# MIDIpod.net
KiCad netlist of a schematic drawn in EAGLE
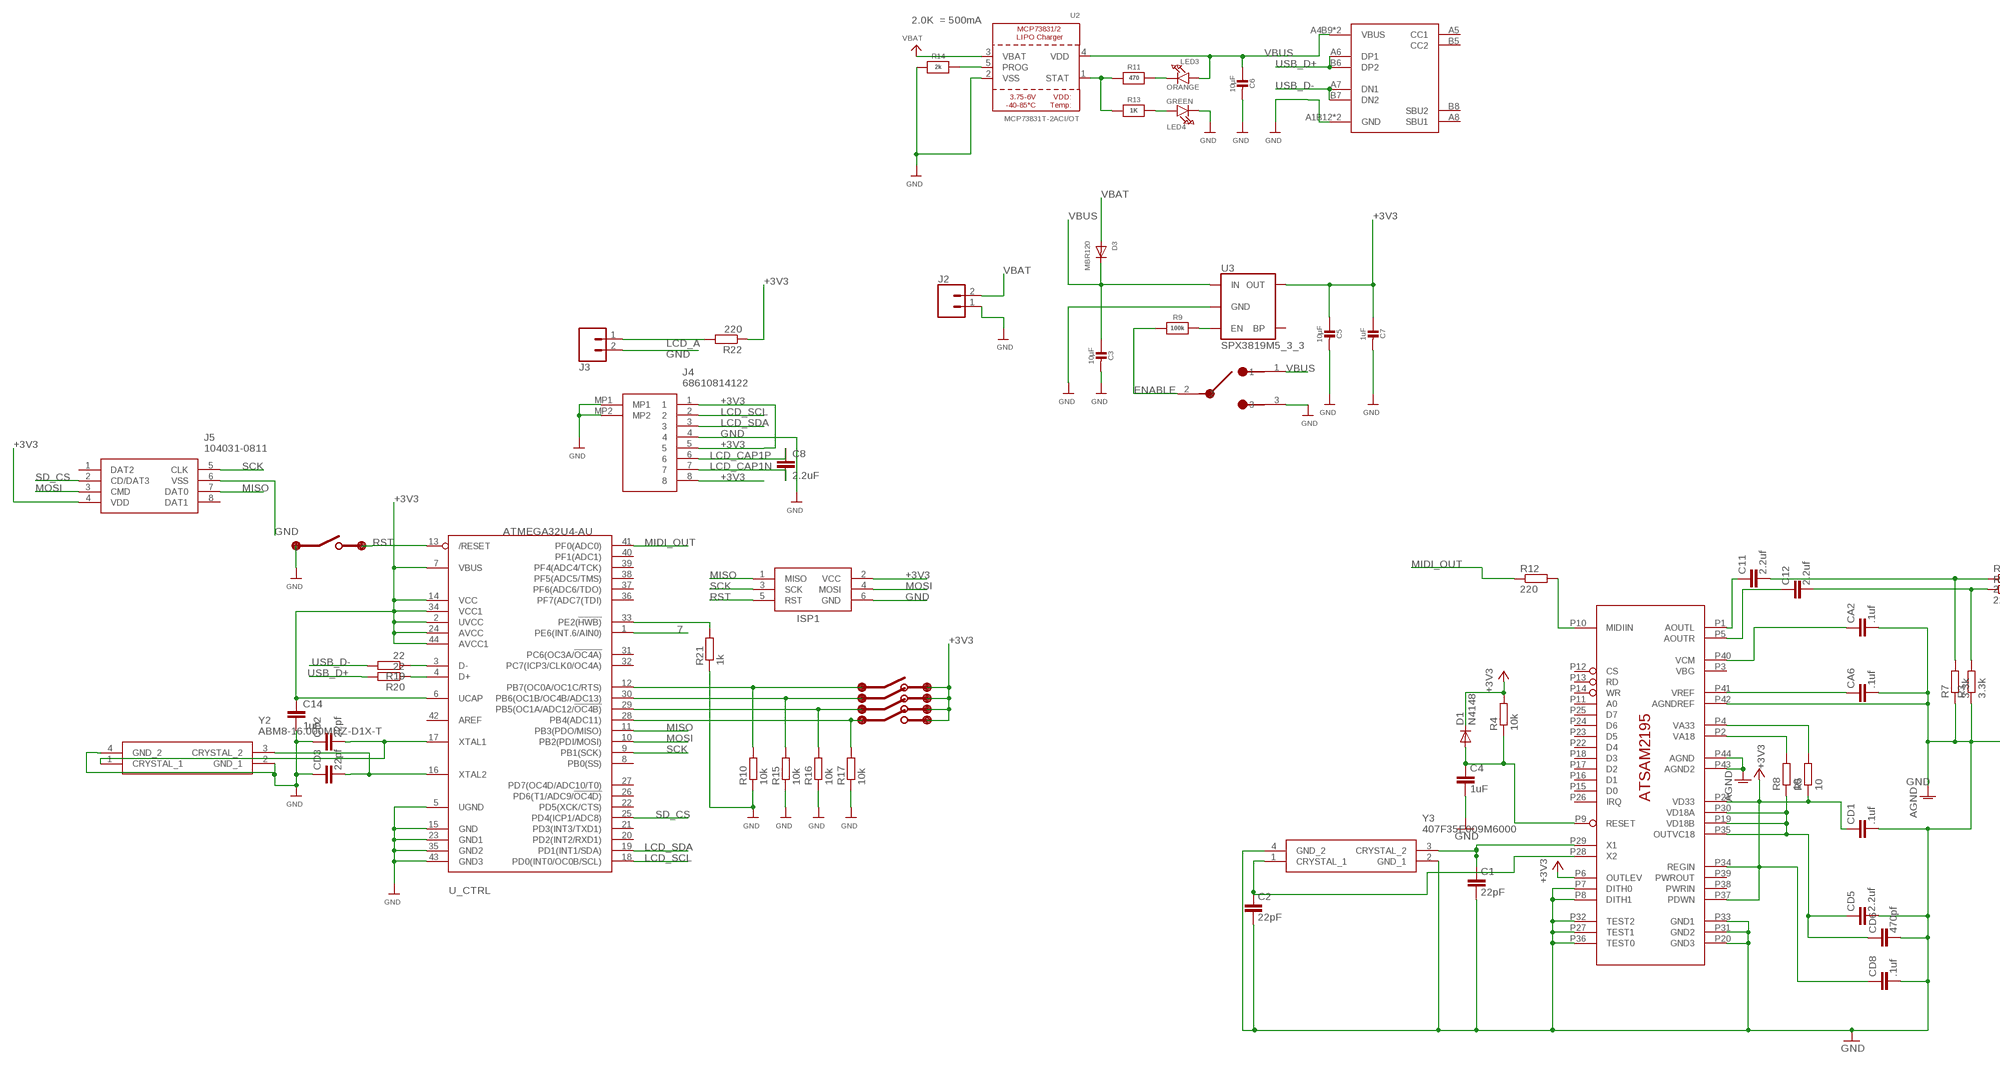
[diagram p0: schematic, sheet 1, part 1 of 2]
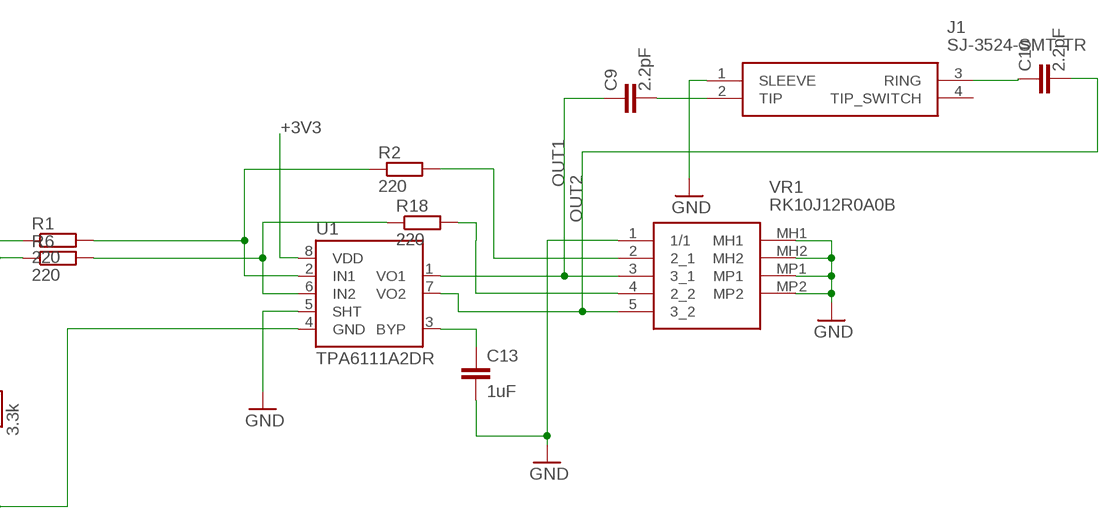
[diagram p1: schematic, sheet 1, part 2 of 2]

(export (version "E")
  (design (tool "Eeschema 10.0.6"))
  (components
    (comp (ref "BUTTON1")
      (value "1U_PAD")
      (footprint "eagle-import:SILICONE_SWITCH")
      (libsource (lib "eagle-import") (part "1U_PAD"))
    )
    (comp (ref "BUTTON2")
      (value "1U_PAD")
      (footprint "eagle-import:SILICONE_SWITCH")
      (libsource (lib "eagle-import") (part "1U_PAD"))
    )
    (comp (ref "BUTTON3")
      (value "1U_PAD")
      (footprint "eagle-import:SILICONE_SWITCH")
      (libsource (lib "eagle-import") (part "1U_PAD"))
    )
    (comp (ref "BUTTON4")
      (value "1U_PAD")
      (footprint "eagle-import:SILICONE_SWITCH")
      (libsource (lib "eagle-import") (part "1U_PAD"))
    )
    (comp (ref "BUTTON5")
      (value "1U_PAD")
      (footprint "eagle-import:SILICONE_SWITCH")
      (libsource (lib "eagle-import") (part "1U_PAD"))
    )
    (comp (ref "C1")
      (value "22pF")
      (footprint "eagle-import:C0603")
      (libsource (lib "eagle-import") (part "C-EUC0603"))
    )
    (comp (ref "C2")
      (value "22pF")
      (footprint "eagle-import:C0603")
      (libsource (lib "eagle-import") (part "C-EUC0603"))
    )
    (comp (ref "C3")
      (value "10µF")
      (footprint "eagle-import:0805-NO")
      (libsource (lib "eagle-import") (part "CAP_CERAMIC0805-NOOUTLINE"))
    )
    (comp (ref "C4")
      (value "1uF")
      (footprint "eagle-import:C0603")
      (libsource (lib "eagle-import") (part "C-EUC0603"))
    )
    (comp (ref "C5")
      (value "10µF")
      (footprint "eagle-import:0805-NO")
      (libsource (lib "eagle-import") (part "CAP_CERAMIC0805-NOOUTLINE"))
    )
    (comp (ref "C6")
      (value "10µF")
      (footprint "eagle-import:0805-NO")
      (libsource (lib "eagle-import") (part "CAP_CERAMIC0805-NOOUTLINE"))
    )
    (comp (ref "C7")
      (value "1uF")
      (footprint "eagle-import:0805-NO")
      (libsource (lib "eagle-import") (part "CAP_CERAMIC0805-NOOUTLINE"))
    )
    (comp (ref "C8")
      (value "2.2uF")
      (footprint "eagle-import:0805")
      (libsource (lib "eagle-import") (part "2.2UF-0805-25V-(+80/-20%)"))
    )
    (comp (ref "C9")
      (value "2.2pF")
      (footprint "eagle-import:C0603")
      (libsource (lib "eagle-import") (part "C-EUC0603"))
    )
    (comp (ref "C10")
      (value "2.2pF")
      (footprint "eagle-import:C0603")
      (libsource (lib "eagle-import") (part "C-EUC0603"))
    )
    (comp (ref "C11")
      (value "2.2uf")
      (footprint "eagle-import:C0603")
      (libsource (lib "eagle-import") (part "C-EUC0603"))
    )
    (comp (ref "C12")
      (value "2.2uf")
      (footprint "eagle-import:C0603")
      (libsource (lib "eagle-import") (part "C-EUC0603"))
    )
    (comp (ref "C13")
      (value "1uF")
      (footprint "eagle-import:0402")
      (libsource (lib "eagle-import") (part "0.1UF-0402-16V-10%"))
    )
    (comp (ref "C14")
      (value "1uF")
      (footprint "eagle-import:0402")
      (libsource (lib "eagle-import") (part "0.1UF-0402-16V-10%"))
    )
    (comp (ref "CA2")
      (value ".1uf")
      (footprint "eagle-import:C0603")
      (libsource (lib "eagle-import") (part "C-EUC0603"))
    )
    (comp (ref "CA6")
      (value ".1uf")
      (footprint "eagle-import:C0603")
      (libsource (lib "eagle-import") (part "C-EUC0603"))
    )
    (comp (ref "CD1")
      (value ".1uf")
      (footprint "eagle-import:C0603")
      (libsource (lib "eagle-import") (part "C-EUC0603"))
    )
    (comp (ref "CD2")
      (value "22pf")
      (footprint "eagle-import:C0603")
      (libsource (lib "eagle-import") (part "C-EUC0603"))
    )
    (comp (ref "CD3")
      (value "22pf")
      (footprint "eagle-import:C0603")
      (libsource (lib "eagle-import") (part "C-EUC0603"))
    )
    (comp (ref "CD5")
      (value "2.2uf")
      (footprint "eagle-import:C0603")
      (libsource (lib "eagle-import") (part "C-EUC0603"))
    )
    (comp (ref "CD6")
      (value "470pf")
      (footprint "eagle-import:C0603")
      (libsource (lib "eagle-import") (part "C-EUC0603"))
    )
    (comp (ref "CD8")
      (value ".1uf")
      (footprint "eagle-import:C0603")
      (libsource (lib "eagle-import") (part "C-EUC0603"))
    )
    (comp (ref "D1")
      (value "N4148")
      (footprint "eagle-import:SOD-123")
      (libsource (lib "eagle-import") (part "DIODESOD-123"))
    )
    (comp (ref "D3")
      (value "MBR120")
      (footprint "eagle-import:SOD-123")
      (libsource (lib "eagle-import") (part "DIODESOD-123"))
    )
    (comp (ref "ISP1")
      (value "AVRISP-6")
      (footprint "eagle-import:AVRISP")
      (libsource (lib "eagle-import") (part "AVRISP-6"))
    )
    (comp (ref "J1")
      (value "SJ-3524-SMT-TR")
      (footprint "eagle-import:SJ-3524-SMT-TR")
      (fields (field (name "MOUSER_PART_NUMBER") "490-SJ-3524-SMT-TR"))
      (libsource (lib "eagle-import") (part "SJ-3524-SMT-TR"))
    )
    (comp (ref "J2")
      (value "CONN_02")
      (footprint "eagle-import:1X02")
      (libsource (lib "eagle-import") (part "CONN_02"))
    )
    (comp (ref "J3")
      (value "CONN_02")
      (footprint "eagle-import:1X02")
      (libsource (lib "eagle-import") (part "CONN_02"))
    )
    (comp (ref "J4")
      (value "68610814122")
      (footprint "eagle-import:68610814122")
      (fields (field (name "MOUSER_PART_NUMBER") "710-68610814122"))
      (libsource (lib "eagle-import") (part "68610814122"))
    )
    (comp (ref "J5")
      (value "104031-0811")
      (footprint "eagle-import:1040310811")
      (fields (field (name "MOUSER_PART_NUMBER") "538-104031-0811"))
      (libsource (lib "eagle-import") (part "104031-0811"))
    )
    (comp (ref "LED3")
      (value "ORANGE")
      (footprint "eagle-import:CHIPLED_0805_NOOUTLINE")
      (libsource (lib "eagle-import") (part "LED0805_NOOUTLINE"))
    )
    (comp (ref "LED4")
      (value "GREEN")
      (footprint "eagle-import:CHIPLED_0805_NOOUTLINE")
      (libsource (lib "eagle-import") (part "LED0805_NOOUTLINE"))
    )
    (comp (ref "POWER_SW")
      (value "ALPSSLIDESW")
      (footprint "eagle-import:SWITCH-SSSS810701")
      (libsource (lib "eagle-import") (part "ALPSSLIDESW"))
    )
    (comp (ref "R1")
      (value "220")
      (footprint "eagle-import:R0603")
      (libsource (lib "eagle-import") (part "R-EU_R0603"))
    )
    (comp (ref "R2")
      (value "220")
      (footprint "eagle-import:R0603")
      (libsource (lib "eagle-import") (part "R-EU_R0603"))
    )
    (comp (ref "R3")
      (value "3.3k")
      (footprint "eagle-import:R0603")
      (libsource (lib "eagle-import") (part "R-EU_R0603"))
    )
    (comp (ref "R4")
      (value "10k")
      (footprint "eagle-import:R0603")
      (libsource (lib "eagle-import") (part "R-EU_R0603"))
    )
    (comp (ref "R5")
      (value "10")
      (footprint "eagle-import:R0603")
      (libsource (lib "eagle-import") (part "R-EU_R0603"))
    )
    (comp (ref "R6")
      (value "220")
      (footprint "eagle-import:R0603")
      (libsource (lib "eagle-import") (part "R-EU_R0603"))
    )
    (comp (ref "R7")
      (value "3.3k")
      (footprint "eagle-import:R0603")
      (libsource (lib "eagle-import") (part "R-EU_R0603"))
    )
    (comp (ref "R8")
      (value "10")
      (footprint "eagle-import:R0603")
      (libsource (lib "eagle-import") (part "R-EU_R0603"))
    )
    (comp (ref "R9")
      (value "100k")
      (footprint "eagle-import:0805-NO")
      (libsource (lib "eagle-import") (part "RESISTOR0805_NOOUTLINE"))
    )
    (comp (ref "R10")
      (value "10k")
      (footprint "eagle-import:R0603")
      (libsource (lib "eagle-import") (part "R-EU_R0603"))
    )
    (comp (ref "R11")
      (value "470")
      (footprint "eagle-import:0805-NO")
      (libsource (lib "eagle-import") (part "RESISTOR0805_NOOUTLINE"))
    )
    (comp (ref "R12")
      (value "220")
      (footprint "eagle-import:R0603")
      (libsource (lib "eagle-import") (part "R-EU_R0603"))
    )
    (comp (ref "R13")
      (value "1K")
      (footprint "eagle-import:0805-NO")
      (libsource (lib "eagle-import") (part "RESISTOR0805_NOOUTLINE"))
    )
    (comp (ref "R14")
      (value "2k")
      (footprint "eagle-import:0805-NO")
      (libsource (lib "eagle-import") (part "RESISTOR0805_NOOUTLINE"))
    )
    (comp (ref "R15")
      (value "10k")
      (footprint "eagle-import:R0603")
      (libsource (lib "eagle-import") (part "R-EU_R0603"))
    )
    (comp (ref "R16")
      (value "10k")
      (footprint "eagle-import:R0603")
      (libsource (lib "eagle-import") (part "R-EU_R0603"))
    )
    (comp (ref "R17")
      (value "10k")
      (footprint "eagle-import:R0603")
      (libsource (lib "eagle-import") (part "R-EU_R0603"))
    )
    (comp (ref "R18")
      (value "220")
      (footprint "eagle-import:R0603")
      (libsource (lib "eagle-import") (part "R-EU_R0603"))
    )
    (comp (ref "R19")
      (value "22")
      (footprint "eagle-import:R0603")
      (libsource (lib "eagle-import") (part "R-EU_R0603"))
    )
    (comp (ref "R20")
      (value "22")
      (footprint "eagle-import:R0603")
      (libsource (lib "eagle-import") (part "R-EU_R0603"))
    )
    (comp (ref "R21")
      (value "1k")
      (footprint "eagle-import:R0603")
      (libsource (lib "eagle-import") (part "R-EU_R0603"))
    )
    (comp (ref "R22")
      (value "220")
      (footprint "eagle-import:R0603")
      (libsource (lib "eagle-import") (part "R-EU_R0603"))
    )
    (comp (ref "U$1")
      (value "ATSAM2195")
      (footprint "eagle-import:ATSAM2195")
      (libsource (lib "eagle-import") (part "ATSAM2195"))
    )
    (comp (ref "U$43")
      (value "TYPE-C-31-M-12")
      (footprint "eagle-import:TYPE-C-31-M-12")
      (libsource (lib "eagle-import") (part "TYPE-C-31-M-12"))
    )
    (comp (ref "U1")
      (value "TPA6111A2DR")
      (footprint "eagle-import:SO08")
      (libsource (lib "eagle-import") (part "TPA6111SMD-T"))
    )
    (comp (ref "U2")
      (value "MCP73831T-2ACI/OT")
      (footprint "eagle-import:SOT23-5")
      (libsource (lib "eagle-import") (part "MCP73831/2"))
    )
    (comp (ref "U3")
      (value "SPX3819M5_3_3")
      (footprint "eagle-import:SOT23-5")
      (libsource (lib "eagle-import") (part "V_REG_SPX3819-SOT23-5"))
    )
    (comp (ref "U_CTRL")
      (value "ATMEGA32U4-AU")
      (footprint "eagle-import:TQFP44")
      (libsource (lib "eagle-import") (part "ATMEGA32U4-AU"))
    )
    (comp (ref "VR1")
      (value "RK10J12R0A0B")
      (footprint "eagle-import:RK10J12R0A0B")
      (fields (field (name "MOUSER_PART_NUMBER") "688-RK10J12R0A0B"))
      (libsource (lib "eagle-import") (part "RK10J12R0A0B"))
    )
    (comp (ref "Y2")
      (value "ABM8-16.000MHZ-D1X-T")
      (footprint "eagle-import:ABM816000MHZD1XT")
      (fields
        (field (name "MANUFACTURER_PART_NUMBER") "ABM8-16.000MHz-D1X-T")
        (field (name "MOUSER_PART_NUMBER") "815-ABM816000MHZD1XT")
      )
      (libsource (lib "eagle-import") (part "ABM8-16.000MHZ-D1X-T"))
    )
    (comp (ref "Y3")
      (value "407F35E009M6000")
      (footprint "eagle-import:407F35E009M6000")
      (fields (field (name "MOUSER_PART_NUMBER") "774-407F35E009M6000"))
      (libsource (lib "eagle-import") (part "407F35E009M6000"))
    )
  )
  (nets
    (net (code "1") (name "+3V3") (class "Default")
      (node (ref "BUTTON1") (pin "P$1") (pinfunction "P$1_P$1") (pintype "bidirectional"))
      (node (ref "BUTTON2") (pin "P$1") (pinfunction "P$1_P$1") (pintype "bidirectional"))
      (node (ref "BUTTON3") (pin "P$1") (pinfunction "P$1_P$1") (pintype "bidirectional"))
      (node (ref "BUTTON4") (pin "P$1") (pinfunction "P$1_P$1") (pintype "bidirectional"))
      (node (ref "C14") (pin "1") (pinfunction "1_1") (pintype "passive"))
      (node (ref "C5") (pin "1") (pinfunction "1_1") (pintype "passive"))
      (node (ref "C7") (pin "1") (pinfunction "1_1") (pintype "passive"))
      (node (ref "CD1") (pin "1") (pinfunction "1_1") (pintype "passive"))
      (node (ref "CD8") (pin "1") (pinfunction "1_1") (pintype "passive"))
      (node (ref "D1") (pin "C") (pinfunction "C_C") (pintype "passive"))
      (node (ref "ISP1") (pin "2") (pinfunction "VCC_2") (pintype "power_in"))
      (node (ref "J4") (pin "1") (pinfunction "1_1") (pintype "bidirectional"))
      (node (ref "J4") (pin "5") (pinfunction "5_5") (pintype "bidirectional"))
      (node (ref "J4") (pin "8") (pinfunction "8_8") (pintype "bidirectional"))
      (node (ref "J5") (pin "4") (pinfunction "VDD_4") (pintype "bidirectional"))
      (node (ref "R22") (pin "1") (pinfunction "1_1") (pintype "passive"))
      (node (ref "R4") (pin "2") (pinfunction "2_2") (pintype "passive"))
      (node (ref "R5") (pin "1") (pinfunction "1_1") (pintype "passive"))
      (node (ref "U$1") (pin "P21") (pinfunction "VD33_P21") (pintype "bidirectional"))
      (node (ref "U$1") (pin "P34") (pinfunction "REGIN_P34") (pintype "bidirectional"))
      (node (ref "U$1") (pin "P37") (pinfunction "PDWN_P37") (pintype "bidirectional"))
      (node (ref "U$1") (pin "P6") (pinfunction "OUTLEV_P6") (pintype "bidirectional"))
      (node (ref "U1") (pin "8") (pinfunction "VDD_8") (pintype "bidirectional"))
      (node (ref "U3") (pin "5") (pinfunction "OUT_5") (pintype "passive"))
      (node (ref "U_CTRL") (pin "14") (pinfunction "VCC_14") (pintype "bidirectional"))
      (node (ref "U_CTRL") (pin "2") (pinfunction "UVCC_2") (pintype "bidirectional"))
      (node (ref "U_CTRL") (pin "24") (pinfunction "AVCC_24") (pintype "bidirectional"))
      (node (ref "U_CTRL") (pin "34") (pinfunction "VCC1_34") (pintype "bidirectional"))
      (node (ref "U_CTRL") (pin "44") (pinfunction "AVCC1_44") (pintype "bidirectional"))
      (node (ref "U_CTRL") (pin "6") (pinfunction "UCAP_6") (pintype "bidirectional"))
      (node (ref "U_CTRL") (pin "7") (pinfunction "VBUS_7") (pintype "bidirectional"))
    )
    (net (code "2") (name "/7") (class "Default")
      (node (ref "U_CTRL") (pin "1") (pinfunction "PE6(INT.6/AIN0)_1") (pintype "bidirectional"))
    )
    (net (code "3") (name "/ENABLE") (class "Default")
      (node (ref "POWER_SW") (pin "2") (pinfunction "2_2") (pintype "bidirectional"))
      (node (ref "R9") (pin "2") (pinfunction "2_2") (pintype "passive"))
    )
    (net (code "4") (name "/LCD_A") (class "Default")
      (node (ref "J3") (pin "1") (pinfunction "1_1") (pintype "passive"))
      (node (ref "R22") (pin "2") (pinfunction "2_2") (pintype "passive"))
    )
    (net (code "5") (name "/LCD_CAP1N") (class "Default")
      (node (ref "C8") (pin "2") (pinfunction "2_2") (pintype "passive"))
      (node (ref "J4") (pin "7") (pinfunction "7_7") (pintype "bidirectional"))
    )
    (net (code "6") (name "/LCD_CAP1P") (class "Default")
      (node (ref "C8") (pin "1") (pinfunction "1_1") (pintype "passive"))
      (node (ref "J4") (pin "6") (pinfunction "6_6") (pintype "bidirectional"))
    )
    (net (code "7") (name "/LCD_SCL") (class "Default")
      (node (ref "J4") (pin "2") (pinfunction "2_2") (pintype "bidirectional"))
      (node (ref "U_CTRL") (pin "18") (pinfunction "PD0(INT0/OC0B/SCL)_18") (pintype "bidirectional"))
    )
    (net (code "8") (name "/LCD_SDA") (class "Default")
      (node (ref "J4") (pin "3") (pinfunction "3_3") (pintype "bidirectional"))
      (node (ref "U_CTRL") (pin "19") (pinfunction "PD1(INT1/SDA)_19") (pintype "bidirectional"))
    )
    (net (code "9") (name "/MIDI_OUT") (class "Default")
      (node (ref "R12") (pin "1") (pinfunction "1_1") (pintype "passive"))
      (node (ref "U_CTRL") (pin "41") (pinfunction "PF0(ADC0)_41") (pintype "bidirectional"))
    )
    (net (code "10") (name "/MISO") (class "Default")
      (node (ref "ISP1") (pin "1") (pinfunction "MISO_1") (pintype "input"))
      (node (ref "J5") (pin "7") (pinfunction "DAT0_7") (pintype "bidirectional"))
      (node (ref "U_CTRL") (pin "11") (pinfunction "PB3(PDO/MISO)_11") (pintype "bidirectional"))
    )
    (net (code "11") (name "/MOSI") (class "Default")
      (node (ref "ISP1") (pin "4") (pinfunction "MOSI_4") (pintype "output"))
      (node (ref "J5") (pin "3") (pinfunction "CMD_3") (pintype "bidirectional"))
      (node (ref "U_CTRL") (pin "10") (pinfunction "PB2(PDI/MOSI)_10") (pintype "bidirectional"))
    )
    (net (code "12") (name "/OUT1") (class "Default")
      (node (ref "C9") (pin "1") (pinfunction "1_1") (pintype "passive"))
      (node (ref "U1") (pin "1") (pinfunction "VO1_1") (pintype "bidirectional"))
      (node (ref "VR1") (pin "3") (pinfunction "3_1_3") (pintype "bidirectional"))
    )
    (net (code "13") (name "/OUT2") (class "Default")
      (node (ref "C10") (pin "2") (pinfunction "2_2") (pintype "passive"))
      (node (ref "U1") (pin "7") (pinfunction "VO2_7") (pintype "bidirectional"))
      (node (ref "VR1") (pin "5") (pinfunction "3_2_5") (pintype "bidirectional"))
    )
    (net (code "14") (name "/RST") (class "Default")
      (node (ref "BUTTON5") (pin "P$1") (pinfunction "P$1_P$1") (pintype "bidirectional"))
      (node (ref "ISP1") (pin "5") (pinfunction "RST_5") (pintype "output"))
      (node (ref "U_CTRL") (pin "13") (pinfunction "/RESET_13") (pintype "bidirectional"))
    )
    (net (code "15") (name "/SCK") (class "Default")
      (node (ref "ISP1") (pin "3") (pinfunction "SCK_3") (pintype "output"))
      (node (ref "J5") (pin "5") (pinfunction "CLK_5") (pintype "bidirectional"))
      (node (ref "U_CTRL") (pin "9") (pinfunction "PB1(SCK)_9") (pintype "bidirectional"))
    )
    (net (code "16") (name "/SD_CS") (class "Default")
      (node (ref "J5") (pin "2") (pinfunction "CD/DAT3_2") (pintype "bidirectional"))
      (node (ref "U_CTRL") (pin "25") (pinfunction "PD4(ICP1/ADC8)_25") (pintype "bidirectional"))
    )
    (net (code "17") (name "/USB_D+") (class "Default")
      (node (ref "R20") (pin "2") (pinfunction "2_2") (pintype "passive"))
      (node (ref "U$43") (pin "A6") (pinfunction "DP1_A6") (pintype "bidirectional"))
      (node (ref "U$43") (pin "B6") (pinfunction "DP2_B6") (pintype "bidirectional"))
    )
    (net (code "18") (name "/USB_D-") (class "Default")
      (node (ref "R19") (pin "2") (pinfunction "2_2") (pintype "passive"))
      (node (ref "U$43") (pin "A7") (pinfunction "DN1_A7") (pintype "bidirectional"))
      (node (ref "U$43") (pin "B7") (pinfunction "DN2_B7") (pintype "bidirectional"))
    )
    (net (code "19") (name "/VBUS") (class "Default")
      (node (ref "C3") (pin "1") (pinfunction "1_1") (pintype "passive"))
      (node (ref "C6") (pin "1") (pinfunction "1_1") (pintype "passive"))
      (node (ref "D3") (pin "C") (pinfunction "C_C") (pintype "passive"))
      (node (ref "LED3") (pin "A") (pinfunction "A_A") (pintype "passive"))
      (node (ref "POWER_SW") (pin "1") (pinfunction "1_1") (pintype "bidirectional"))
      (node (ref "U$43") (pin "A4B9") (pinfunction "VBUS_A4B9") (pintype "bidirectional"))
      (node (ref "U$43") (pin "B4A9") (pinfunction "VBUS_B4A9") (pintype "bidirectional"))
      (node (ref "U2") (pin "4") (pinfunction "VDD_4") (pintype "power_in"))
      (node (ref "U3") (pin "1") (pinfunction "IN_1") (pintype "input"))
    )
    (net (code "20") (name "AGND") (class "Default")
      (node (ref "BUTTON5") (pin "P$2") (pinfunction "P$2_P$2") (pintype "bidirectional"))
      (node (ref "C1") (pin "2") (pinfunction "2_2") (pintype "passive"))
      (node (ref "C13") (pin "2") (pinfunction "2_2") (pintype "passive"))
      (node (ref "C14") (pin "2") (pinfunction "2_2") (pintype "passive"))
      (node (ref "C2") (pin "2") (pinfunction "2_2") (pintype "passive"))
      (node (ref "C3") (pin "2") (pinfunction "2_2") (pintype "passive"))
      (node (ref "C4") (pin "2") (pinfunction "2_2") (pintype "passive"))
      (node (ref "C5") (pin "2") (pinfunction "2_2") (pintype "passive"))
      (node (ref "C6") (pin "2") (pinfunction "2_2") (pintype "passive"))
      (node (ref "C7") (pin "2") (pinfunction "2_2") (pintype "passive"))
      (node (ref "CA2") (pin "2") (pinfunction "2_2") (pintype "passive"))
      (node (ref "CA6") (pin "2") (pinfunction "2_2") (pintype "passive"))
      (node (ref "CD1") (pin "2") (pinfunction "2_2") (pintype "passive"))
      (node (ref "CD2") (pin "1") (pinfunction "1_1") (pintype "passive"))
      (node (ref "CD3") (pin "1") (pinfunction "1_1") (pintype "passive"))
      (node (ref "CD5") (pin "2") (pinfunction "2_2") (pintype "passive"))
      (node (ref "CD6") (pin "2") (pinfunction "2_2") (pintype "passive"))
      (node (ref "CD8") (pin "2") (pinfunction "2_2") (pintype "passive"))
      (node (ref "ISP1") (pin "6") (pinfunction "GND_6") (pintype "power_in"))
      (node (ref "J1") (pin "1") (pinfunction "SLEEVE_1") (pintype "bidirectional"))
      (node (ref "J2") (pin "1") (pinfunction "1_1") (pintype "passive"))
      (node (ref "J3") (pin "2") (pinfunction "2_2") (pintype "passive"))
      (node (ref "J4") (pin "4") (pinfunction "4_4") (pintype "bidirectional"))
      (node (ref "J4") (pin "MP1") (pinfunction "MP1_MP1") (pintype "bidirectional"))
      (node (ref "J4") (pin "MP2") (pinfunction "MP2_MP2") (pintype "bidirectional"))
      (node (ref "J5") (pin "6") (pinfunction "VSS_6") (pintype "bidirectional"))
      (node (ref "LED4") (pin "C") (pinfunction "C_C") (pintype "passive"))
      (node (ref "POWER_SW") (pin "3") (pinfunction "3_3") (pintype "bidirectional"))
      (node (ref "R10") (pin "1") (pinfunction "1_1") (pintype "passive"))
      (node (ref "R14") (pin "2") (pinfunction "2_2") (pintype "passive"))
      (node (ref "R15") (pin "1") (pinfunction "1_1") (pintype "passive"))
      (node (ref "R16") (pin "1") (pinfunction "1_1") (pintype "passive"))
      (node (ref "R17") (pin "1") (pinfunction "1_1") (pintype "passive"))
      (node (ref "R21") (pin "1") (pinfunction "1_1") (pintype "passive"))
      (node (ref "R3") (pin "1") (pinfunction "1_1") (pintype "passive"))
      (node (ref "R7") (pin "1") (pinfunction "1_1") (pintype "passive"))
      (node (ref "U$1") (pin "P20") (pinfunction "GND3_P20") (pintype "bidirectional"))
      (node (ref "U$1") (pin "P27") (pinfunction "TEST1_P27") (pintype "bidirectional"))
      (node (ref "U$1") (pin "P31") (pinfunction "GND2_P31") (pintype "bidirectional"))
      (node (ref "U$1") (pin "P32") (pinfunction "TEST2_P32") (pintype "bidirectional"))
      (node (ref "U$1") (pin "P33") (pinfunction "GND1_P33") (pintype "bidirectional"))
      (node (ref "U$1") (pin "P36") (pinfunction "TEST0_P36") (pintype "bidirectional"))
      (node (ref "U$1") (pin "P42") (pinfunction "AGNDREF_P42") (pintype "bidirectional"))
      (node (ref "U$1") (pin "P43") (pinfunction "AGND2_P43") (pintype "bidirectional"))
      (node (ref "U$1") (pin "P44") (pinfunction "AGND_P44") (pintype "bidirectional"))
      (node (ref "U$1") (pin "P7") (pinfunction "DITH0_P7") (pintype "bidirectional"))
      (node (ref "U$1") (pin "P8") (pinfunction "DITH1_P8") (pintype "bidirectional"))
      (node (ref "U$43") (pin "A1B12") (pinfunction "GND_A1B12") (pintype "bidirectional"))
      (node (ref "U$43") (pin "B1A12") (pinfunction "GND_B1A12") (pintype "bidirectional"))
      (node (ref "U1") (pin "4") (pinfunction "GND_4") (pintype "bidirectional"))
      (node (ref "U1") (pin "5") (pinfunction "SHT_5") (pintype "bidirectional"))
      (node (ref "U2") (pin "2") (pinfunction "VSS_2") (pintype "power_in"))
      (node (ref "U3") (pin "2") (pinfunction "GND_2") (pintype "input"))
      (node (ref "U_CTRL") (pin "15") (pinfunction "GND_15") (pintype "bidirectional"))
      (node (ref "U_CTRL") (pin "23") (pinfunction "GND1_23") (pintype "bidirectional"))
      (node (ref "U_CTRL") (pin "35") (pinfunction "GND2_35") (pintype "bidirectional"))
      (node (ref "U_CTRL") (pin "43") (pinfunction "GND3_43") (pintype "bidirectional"))
      (node (ref "U_CTRL") (pin "5") (pinfunction "UGND_5") (pintype "bidirectional"))
      (node (ref "VR1") (pin "1") (pinfunction "1/1_1") (pintype "bidirectional"))
      (node (ref "VR1") (pin "MH1") (pinfunction "MH1_MH1") (pintype "bidirectional"))
      (node (ref "VR1") (pin "MH2") (pinfunction "MH2_MH2") (pintype "bidirectional"))
      (node (ref "VR1") (pin "MP1") (pinfunction "MP1_MP1") (pintype "bidirectional"))
      (node (ref "VR1") (pin "MP2") (pinfunction "MP2_MP2") (pintype "bidirectional"))
      (node (ref "Y2") (pin "2") (pinfunction "GND_1_2") (pintype "bidirectional"))
      (node (ref "Y2") (pin "4") (pinfunction "GND_2_4") (pintype "bidirectional"))
      (node (ref "Y3") (pin "2") (pinfunction "GND_1_2") (pintype "bidirectional"))
      (node (ref "Y3") (pin "4") (pinfunction "GND_2_4") (pintype "bidirectional"))
    )
    (net (code "21") (name "Net-(C11-Pad2)") (class "Default")
      (node (ref "C11") (pin "2") (pinfunction "2_2") (pintype "passive"))
      (node (ref "R1") (pin "1") (pinfunction "1_1") (pintype "passive"))
      (node (ref "R7") (pin "2") (pinfunction "2_2") (pintype "passive"))
    )
    (net (code "22") (name "Net-(C12-Pad2)") (class "Default")
      (node (ref "C12") (pin "2") (pinfunction "2_2") (pintype "passive"))
      (node (ref "R3") (pin "2") (pinfunction "2_2") (pintype "passive"))
      (node (ref "R6") (pin "1") (pinfunction "1_1") (pintype "passive"))
    )
    (net (code "23") (name "Net-(J1-RING)") (class "Default")
      (node (ref "C10") (pin "1") (pinfunction "1_1") (pintype "passive"))
      (node (ref "J1") (pin "3") (pinfunction "RING_3") (pintype "bidirectional"))
    )
    (net (code "24") (name "Net-(J1-TIP)") (class "Default")
      (node (ref "C9") (pin "2") (pinfunction "2_2") (pintype "passive"))
      (node (ref "J1") (pin "2") (pinfunction "TIP_2") (pintype "bidirectional"))
    )
    (net (code "25") (name "Net-(LED3-PadC)") (class "Default")
      (node (ref "LED3") (pin "C") (pinfunction "C_C") (pintype "passive"))
      (node (ref "R11") (pin "1") (pinfunction "1_1") (pintype "passive"))
    )
    (net (code "26") (name "Net-(LED4-PadA)") (class "Default")
      (node (ref "LED4") (pin "A") (pinfunction "A_A") (pintype "passive"))
      (node (ref "R13") (pin "1") (pinfunction "1_1") (pintype "passive"))
    )
    (net (code "27") (name "Net-(U$1-AOUTL)") (class "Default")
      (node (ref "C11") (pin "1") (pinfunction "1_1") (pintype "passive"))
      (node (ref "U$1") (pin "P1") (pinfunction "AOUTL_P1") (pintype "bidirectional"))
    )
    (net (code "28") (name "Net-(U$1-AOUTR)") (class "Default")
      (node (ref "C12") (pin "1") (pinfunction "1_1") (pintype "passive"))
      (node (ref "U$1") (pin "P5") (pinfunction "AOUTR_P5") (pintype "bidirectional"))
    )
    (net (code "29") (name "Net-(U$1-MIDIIN)") (class "Default")
      (node (ref "R12") (pin "2") (pinfunction "2_2") (pintype "passive"))
      (node (ref "U$1") (pin "P10") (pinfunction "MIDIIN_P10") (pintype "bidirectional"))
    )
    (net (code "30") (name "Net-(U$1-OUTVC18)") (class "Default")
      (node (ref "CD5") (pin "1") (pinfunction "1_1") (pintype "passive"))
      (node (ref "CD6") (pin "1") (pinfunction "1_1") (pintype "passive"))
      (node (ref "R8") (pin "1") (pinfunction "1_1") (pintype "passive"))
      (node (ref "U$1") (pin "P19") (pinfunction "VD18B_P19") (pintype "bidirectional"))
      (node (ref "U$1") (pin "P30") (pinfunction "VD18A_P30") (pintype "bidirectional"))
      (node (ref "U$1") (pin "P35") (pinfunction "OUTVC18_P35") (pintype "bidirectional"))
    )
    (net (code "31") (name "Net-(U$1-RESET)") (class "Default")
      (node (ref "C4") (pin "1") (pinfunction "1_1") (pintype "passive"))
      (node (ref "D1") (pin "A") (pinfunction "A_A") (pintype "passive"))
      (node (ref "R4") (pin "1") (pinfunction "1_1") (pintype "passive"))
      (node (ref "U$1") (pin "P9") (pinfunction "RESET_P9") (pintype "bidirectional"))
    )
    (net (code "32") (name "Net-(U$1-VA18)") (class "Default")
      (node (ref "R8") (pin "2") (pinfunction "2_2") (pintype "passive"))
      (node (ref "U$1") (pin "P2") (pinfunction "VA18_P2") (pintype "bidirectional"))
    )
    (net (code "33") (name "Net-(U$1-VA33)") (class "Default")
      (node (ref "R5") (pin "2") (pinfunction "2_2") (pintype "passive"))
      (node (ref "U$1") (pin "P4") (pinfunction "VA33_P4") (pintype "bidirectional"))
    )
    (net (code "34") (name "Net-(U$1-VCM)") (class "Default")
      (node (ref "CA2") (pin "1") (pinfunction "1_1") (pintype "passive"))
      (node (ref "U$1") (pin "P40") (pinfunction "VCM_P40") (pintype "bidirectional"))
    )
    (net (code "35") (name "Net-(U$1-VREF)") (class "Default")
      (node (ref "CA6") (pin "1") (pinfunction "1_1") (pintype "passive"))
      (node (ref "U$1") (pin "P41") (pinfunction "VREF_P41") (pintype "bidirectional"))
    )
    (net (code "36") (name "Net-(U$1-X1)") (class "Default")
      (node (ref "C1") (pin "1") (pinfunction "1_1") (pintype "passive"))
      (node (ref "U$1") (pin "P29") (pinfunction "X1_P29") (pintype "bidirectional"))
      (node (ref "Y3") (pin "3") (pinfunction "CRYSTAL_2_3") (pintype "bidirectional"))
    )
    (net (code "37") (name "Net-(U$1-X2)") (class "Default")
      (node (ref "C2") (pin "1") (pinfunction "1_1") (pintype "passive"))
      (node (ref "U$1") (pin "P28") (pinfunction "X2_P28") (pintype "bidirectional"))
      (node (ref "Y3") (pin "1") (pinfunction "CRYSTAL_1_1") (pintype "bidirectional"))
    )
    (net (code "38") (name "Net-(U1-BYP)") (class "Default")
      (node (ref "C13") (pin "1") (pinfunction "1_1") (pintype "passive"))
      (node (ref "U1") (pin "3") (pinfunction "BYP_3") (pintype "bidirectional"))
    )
    (net (code "39") (name "Net-(U1-IN1)") (class "Default")
      (node (ref "R1") (pin "2") (pinfunction "2_2") (pintype "passive"))
      (node (ref "R2") (pin "1") (pinfunction "1_1") (pintype "passive"))
      (node (ref "U1") (pin "2") (pinfunction "IN1_2") (pintype "bidirectional"))
    )
    (net (code "40") (name "Net-(U1-IN2)") (class "Default")
      (node (ref "R18") (pin "1") (pinfunction "1_1") (pintype "passive"))
      (node (ref "R6") (pin "2") (pinfunction "2_2") (pintype "passive"))
      (node (ref "U1") (pin "6") (pinfunction "IN2_6") (pintype "bidirectional"))
    )
    (net (code "41") (name "Net-(U2-PROG)") (class "Default")
      (node (ref "R14") (pin "1") (pinfunction "1_1") (pintype "passive"))
      (node (ref "U2") (pin "5") (pinfunction "PROG_5") (pintype "input"))
    )
    (net (code "42") (name "Net-(U2-STAT)") (class "Default")
      (node (ref "R11") (pin "2") (pinfunction "2_2") (pintype "passive"))
      (node (ref "R13") (pin "2") (pinfunction "2_2") (pintype "passive"))
      (node (ref "U2") (pin "1") (pinfunction "STAT_1") (pintype "output"))
    )
    (net (code "43") (name "Net-(U3-EN)") (class "Default")
      (node (ref "R9") (pin "1") (pinfunction "1_1") (pintype "passive"))
      (node (ref "U3") (pin "3") (pinfunction "EN_3") (pintype "input"))
    )
    (net (code "44") (name "Net-(U_CTRL-D+)") (class "Default")
      (node (ref "R20") (pin "1") (pinfunction "1_1") (pintype "passive"))
      (node (ref "U_CTRL") (pin "4") (pinfunction "D+_4") (pintype "bidirectional"))
    )
    (net (code "45") (name "Net-(U_CTRL-D-)") (class "Default")
      (node (ref "R19") (pin "1") (pinfunction "1_1") (pintype "passive"))
      (node (ref "U_CTRL") (pin "3") (pinfunction "D-_3") (pintype "bidirectional"))
    )
    (net (code "46") (name "Net-(U_CTRL-PB4(ADC11))") (class "Default")
      (node (ref "BUTTON4") (pin "P$2") (pinfunction "P$2_P$2") (pintype "bidirectional"))
      (node (ref "R17") (pin "2") (pinfunction "2_2") (pintype "passive"))
      (node (ref "U_CTRL") (pin "28") (pinfunction "PB4(ADC11)_28") (pintype "bidirectional"))
    )
    (net (code "47") (name "Net-(U_CTRL-PB5(OC1A{slash}ADC12{slash}~{OC4B}))") (class "Default")
      (node (ref "BUTTON3") (pin "P$2") (pinfunction "P$2_P$2") (pintype "bidirectional"))
      (node (ref "R16") (pin "2") (pinfunction "2_2") (pintype "passive"))
      (node (ref "U_CTRL") (pin "29") (pinfunction "PB5(OC1A/ADC12/~{OC4B})_29") (pintype "bidirectional"))
    )
    (net (code "48") (name "Net-(U_CTRL-PB6(OC1B{slash}OC4B{slash}ADC13))") (class "Default")
      (node (ref "BUTTON2") (pin "P$2") (pinfunction "P$2_P$2") (pintype "bidirectional"))
      (node (ref "R15") (pin "2") (pinfunction "2_2") (pintype "passive"))
      (node (ref "U_CTRL") (pin "30") (pinfunction "PB6(OC1B/OC4B/ADC13)_30") (pintype "bidirectional"))
    )
    (net (code "49") (name "Net-(U_CTRL-PB7(OC0A{slash}OC1C{slash}RTS))") (class "Default")
      (node (ref "BUTTON1") (pin "P$2") (pinfunction "P$2_P$2") (pintype "bidirectional"))
      (node (ref "R10") (pin "2") (pinfunction "2_2") (pintype "passive"))
      (node (ref "U_CTRL") (pin "12") (pinfunction "PB7(OC0A/OC1C/RTS)_12") (pintype "bidirectional"))
    )
    (net (code "50") (name "Net-(U_CTRL-PE2(~{HWB}))") (class "Default")
      (node (ref "R21") (pin "2") (pinfunction "2_2") (pintype "passive"))
      (node (ref "U_CTRL") (pin "33") (pinfunction "PE2(~{HWB})_33") (pintype "bidirectional"))
    )
    (net (code "51") (name "Net-(U_CTRL-XTAL1)") (class "Default")
      (node (ref "CD2") (pin "2") (pinfunction "2_2") (pintype "passive"))
      (node (ref "U_CTRL") (pin "17") (pinfunction "XTAL1_17") (pintype "bidirectional"))
      (node (ref "Y2") (pin "1") (pinfunction "CRYSTAL_1_1") (pintype "bidirectional"))
    )
    (net (code "52") (name "Net-(U_CTRL-XTAL2)") (class "Default")
      (node (ref "CD3") (pin "2") (pinfunction "2_2") (pintype "passive"))
      (node (ref "U_CTRL") (pin "16") (pinfunction "XTAL2_16") (pintype "bidirectional"))
      (node (ref "Y2") (pin "3") (pinfunction "CRYSTAL_2_3") (pintype "bidirectional"))
    )
    (net (code "53") (name "Net-(VR1-2_1)") (class "Default")
      (node (ref "R2") (pin "2") (pinfunction "2_2") (pintype "passive"))
      (node (ref "VR1") (pin "2") (pinfunction "2_1_2") (pintype "bidirectional"))
    )
    (net (code "54") (name "Net-(VR1-2_2)") (class "Default")
      (node (ref "R18") (pin "2") (pinfunction "2_2") (pintype "passive"))
      (node (ref "VR1") (pin "4") (pinfunction "2_2_4") (pintype "bidirectional"))
    )
    (net (code "55") (name "VBAT") (class "Default")
      (node (ref "D3") (pin "A") (pinfunction "A_A") (pintype "passive"))
      (node (ref "J2") (pin "2") (pinfunction "2_2") (pintype "passive"))
      (node (ref "U2") (pin "3") (pinfunction "VBAT_3") (pintype "power_in"))
    )
    (net (code "56") (name "unconnected-(J1-TIP_SWITCH-Pad4)") (class "Default")
      (node (ref "J1") (pin "4") (pinfunction "TIP_SWITCH_4") (pintype "bidirectional"))
    )
    (net (code "57") (name "unconnected-(J5-DAT1-Pad8)") (class "Default")
      (node (ref "J5") (pin "8") (pinfunction "DAT1_8") (pintype "bidirectional"))
    )
    (net (code "58") (name "unconnected-(J5-DAT2-Pad1)") (class "Default")
      (node (ref "J5") (pin "1") (pinfunction "DAT2_1") (pintype "bidirectional"))
    )
    (net (code "59") (name "unconnected-(U$1-A0-PadP11)") (class "Default")
      (node (ref "U$1") (pin "P11") (pinfunction "A0_P11") (pintype "bidirectional"))
    )
    (net (code "60") (name "unconnected-(U$1-CS-PadP12)") (class "Default")
      (node (ref "U$1") (pin "P12") (pinfunction "CS_P12") (pintype "bidirectional"))
    )
    (net (code "61") (name "unconnected-(U$1-D0-PadP15)") (class "Default")
      (node (ref "U$1") (pin "P15") (pinfunction "D0_P15") (pintype "bidirectional"))
    )
    (net (code "62") (name "unconnected-(U$1-D1-PadP16)") (class "Default")
      (node (ref "U$1") (pin "P16") (pinfunction "D1_P16") (pintype "bidirectional"))
    )
    (net (code "63") (name "unconnected-(U$1-D2-PadP17)") (class "Default")
      (node (ref "U$1") (pin "P17") (pinfunction "D2_P17") (pintype "bidirectional"))
    )
    (net (code "64") (name "unconnected-(U$1-D3-PadP18)") (class "Default")
      (node (ref "U$1") (pin "P18") (pinfunction "D3_P18") (pintype "bidirectional"))
    )
    (net (code "65") (name "unconnected-(U$1-D4-PadP22)") (class "Default")
      (node (ref "U$1") (pin "P22") (pinfunction "D4_P22") (pintype "bidirectional"))
    )
    (net (code "66") (name "unconnected-(U$1-D5-PadP23)") (class "Default")
      (node (ref "U$1") (pin "P23") (pinfunction "D5_P23") (pintype "bidirectional"))
    )
    (net (code "67") (name "unconnected-(U$1-D6-PadP24)") (class "Default")
      (node (ref "U$1") (pin "P24") (pinfunction "D6_P24") (pintype "bidirectional"))
    )
    (net (code "68") (name "unconnected-(U$1-D7-PadP25)") (class "Default")
      (node (ref "U$1") (pin "P25") (pinfunction "D7_P25") (pintype "bidirectional"))
    )
    (net (code "69") (name "unconnected-(U$1-IRQ-PadP26)") (class "Default")
      (node (ref "U$1") (pin "P26") (pinfunction "IRQ_P26") (pintype "bidirectional"))
    )
    (net (code "70") (name "unconnected-(U$1-PWRIN-PadP38)") (class "Default")
      (node (ref "U$1") (pin "P38") (pinfunction "PWRIN_P38") (pintype "bidirectional"))
    )
    (net (code "71") (name "unconnected-(U$1-PWROUT-PadP39)") (class "Default")
      (node (ref "U$1") (pin "P39") (pinfunction "PWROUT_P39") (pintype "bidirectional"))
    )
    (net (code "72") (name "unconnected-(U$1-RD-PadP13)") (class "Default")
      (node (ref "U$1") (pin "P13") (pinfunction "RD_P13") (pintype "bidirectional"))
    )
    (net (code "73") (name "unconnected-(U$1-VBG-PadP3)") (class "Default")
      (node (ref "U$1") (pin "P3") (pinfunction "VBG_P3") (pintype "bidirectional"))
    )
    (net (code "74") (name "unconnected-(U$1-WR-PadP14)") (class "Default")
      (node (ref "U$1") (pin "P14") (pinfunction "WR_P14") (pintype "bidirectional"))
    )
    (net (code "75") (name "unconnected-(U$43-CC1-PadA5)") (class "Default")
      (node (ref "U$43") (pin "A5") (pinfunction "CC1_A5") (pintype "bidirectional"))
    )
    (net (code "76") (name "unconnected-(U$43-CC2-PadB5)") (class "Default")
      (node (ref "U$43") (pin "B5") (pinfunction "CC2_B5") (pintype "bidirectional"))
    )
    (net (code "77") (name "unconnected-(U$43-SBU1-PadA8)") (class "Default")
      (node (ref "U$43") (pin "A8") (pinfunction "SBU1_A8") (pintype "bidirectional"))
    )
    (net (code "78") (name "unconnected-(U$43-SBU2-PadB8)") (class "Default")
      (node (ref "U$43") (pin "B8") (pinfunction "SBU2_B8") (pintype "bidirectional"))
    )
    (net (code "79") (name "unconnected-(U3-BP-Pad4)") (class "Default")
      (node (ref "U3") (pin "4") (pinfunction "BP_4") (pintype "input"))
    )
    (net (code "80") (name "unconnected-(U_CTRL-AREF-Pad42)") (class "Default")
      (node (ref "U_CTRL") (pin "42") (pinfunction "AREF_42") (pintype "bidirectional"))
    )
    (net (code "81") (name "unconnected-(U_CTRL-PB0(SS)-Pad8)") (class "Default")
      (node (ref "U_CTRL") (pin "8") (pinfunction "PB0(SS)_8") (pintype "bidirectional"))
    )
    (net (code "82") (name "unconnected-(U_CTRL-PC6(OC3A{slash}~{OC4A})-Pad31)") (class "Default")
      (node (ref "U_CTRL") (pin "31") (pinfunction "PC6(OC3A/~{OC4A})_31") (pintype "bidirectional"))
    )
    (net (code "83") (name "unconnected-(U_CTRL-PC7(ICP3{slash}CLK0{slash}OC4A)-Pad32)") (class "Default")
      (node (ref "U_CTRL") (pin "32") (pinfunction "PC7(ICP3/CLK0/OC4A)_32") (pintype "bidirectional"))
    )
    (net (code "84") (name "unconnected-(U_CTRL-PD2(INT2{slash}RXD1)-Pad20)") (class "Default")
      (node (ref "U_CTRL") (pin "20") (pinfunction "PD2(INT2/RXD1)_20") (pintype "bidirectional"))
    )
    (net (code "85") (name "unconnected-(U_CTRL-PD3(INT3{slash}TXD1)-Pad21)") (class "Default")
      (node (ref "U_CTRL") (pin "21") (pinfunction "PD3(INT3/TXD1)_21") (pintype "bidirectional"))
    )
    (net (code "86") (name "unconnected-(U_CTRL-PD5(XCK{slash}CTS)-Pad22)") (class "Default")
      (node (ref "U_CTRL") (pin "22") (pinfunction "PD5(XCK/CTS)_22") (pintype "bidirectional"))
    )
    (net (code "87") (name "unconnected-(U_CTRL-PD6(T1{slash}ADC9{slash}~{OC4D})-Pad26)") (class "Default")
      (node (ref "U_CTRL") (pin "26") (pinfunction "PD6(T1/ADC9/~{OC4D})_26") (pintype "bidirectional"))
    )
    (net (code "88") (name "unconnected-(U_CTRL-PD7(OC4D{slash}ADC10{slash}T0)-Pad27)") (class "Default")
      (node (ref "U_CTRL") (pin "27") (pinfunction "PD7(OC4D/ADC10/T0)_27") (pintype "bidirectional"))
    )
    (net (code "89") (name "unconnected-(U_CTRL-PF1(ADC1)-Pad40)") (class "Default")
      (node (ref "U_CTRL") (pin "40") (pinfunction "PF1(ADC1)_40") (pintype "bidirectional"))
    )
    (net (code "90") (name "unconnected-(U_CTRL-PF4(ADC4{slash}TCK)-Pad39)") (class "Default")
      (node (ref "U_CTRL") (pin "39") (pinfunction "PF4(ADC4/TCK)_39") (pintype "bidirectional"))
    )
    (net (code "91") (name "unconnected-(U_CTRL-PF5(ADC5{slash}TMS)-Pad38)") (class "Default")
      (node (ref "U_CTRL") (pin "38") (pinfunction "PF5(ADC5/TMS)_38") (pintype "bidirectional"))
    )
    (net (code "92") (name "unconnected-(U_CTRL-PF6(ADC6{slash}TDO)-Pad37)") (class "Default")
      (node (ref "U_CTRL") (pin "37") (pinfunction "PF6(ADC6/TDO)_37") (pintype "bidirectional"))
    )
    (net (code "93") (name "unconnected-(U_CTRL-PF7(ADC7(TDI)-Pad36)") (class "Default")
      (node (ref "U_CTRL") (pin "36") (pinfunction "PF7(ADC7(TDI)_36") (pintype "bidirectional"))
    )
  )
)
